# iotv3_595.net
KiCad netlist of a schematic drawn in Altium Designer
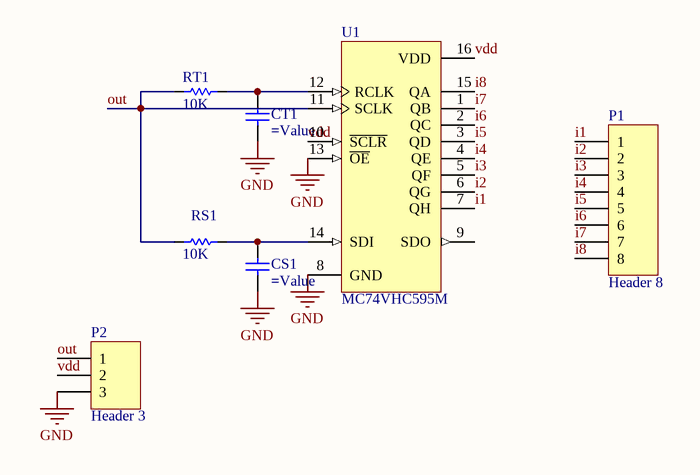
[diagram p0: iotv3 595.SchDoc]

(export (version "E")
  (design (tool "Eeschema 10.0.6"))
  (components
    (comp (ref "CS1")
      (value "~")
      (footprint "CAP 1206")
      (description "Capacitor")
      (libsource (lib "AltiumLib1") (part "Capacitor"))
    )
    (comp (ref "CT1")
      (value "~")
      (footprint "CAP 1206")
      (description "Capacitor")
      (libsource (lib "AltiumLib1") (part "Capacitor"))
    )
    (comp (ref "P1")
      (value "Header 8")
      (footprint "HDR1X8")
      (description "Header, 8-Pin")
      (fields (field (name "PUBLISHER") "Altium Limited"))
      (libsource (lib "Miscellaneous Connectors") (part "Header 8"))
    )
    (comp (ref "P2")
      (value "Header 3")
      (footprint "HDR1X3")
      (description "Header, 3-Pin")
      (fields (field (name "PUBLISHER") "Altium Limited"))
      (libsource (lib "Miscellaneous Connectors") (part "Header 3"))
    )
    (comp (ref "RS1")
      (value "10K")
      (footprint "RES 1206 (3216X08L)")
      (description "Resistor")
      (fields (field (name "TOLERANCE") "5%") (field (name "POWER") "1/4 W"))
      (libsource (lib "AltiumLib1") (part "Resistor"))
    )
    (comp (ref "RT1")
      (value "10K")
      (footprint "RES 1206 (3216X08L)")
      (description "Resistor")
      (fields (field (name "TOLERANCE") "5%") (field (name "POWER") "1/4 W"))
      (libsource (lib "AltiumLib1") (part "Resistor"))
    )
    (comp (ref "U1")
      (value "MC74VHC595M")
      (footprint "966-01_N")
      (description "8-Bit 3-State Shift Register with Output Storage Register")
      (fields (field (name "PUBLISHER") "Altium Limited"))
      (libsource (lib "ON Semi Logic Register") (part "MC74VHC595M"))
    )
  )
  (nets
    (net (code "1") (name "/i1") (class "Default")
      (node (ref "P1") (pin "1") (pinfunction "1_1") (pintype "passive"))
      (node (ref "U1") (pin "7") (pinfunction "QH_7") (pintype "tri_state"))
    )
    (net (code "2") (name "/i2") (class "Default")
      (node (ref "P1") (pin "2") (pinfunction "2_2") (pintype "passive"))
      (node (ref "U1") (pin "6") (pinfunction "QG_6") (pintype "tri_state"))
    )
    (net (code "3") (name "/i3") (class "Default")
      (node (ref "P1") (pin "3") (pinfunction "3_3") (pintype "passive"))
      (node (ref "U1") (pin "5") (pinfunction "QF_5") (pintype "tri_state"))
    )
    (net (code "4") (name "/i4") (class "Default")
      (node (ref "P1") (pin "4") (pinfunction "4_4") (pintype "passive"))
      (node (ref "U1") (pin "4") (pinfunction "QE_4") (pintype "tri_state"))
    )
    (net (code "5") (name "/i5") (class "Default")
      (node (ref "P1") (pin "5") (pinfunction "5_5") (pintype "passive"))
      (node (ref "U1") (pin "3") (pinfunction "QD_3") (pintype "tri_state"))
    )
    (net (code "6") (name "/i6") (class "Default")
      (node (ref "P1") (pin "6") (pinfunction "6_6") (pintype "passive"))
      (node (ref "U1") (pin "2") (pinfunction "QC_2") (pintype "tri_state"))
    )
    (net (code "7") (name "/i7") (class "Default")
      (node (ref "P1") (pin "7") (pinfunction "7_7") (pintype "passive"))
      (node (ref "U1") (pin "1") (pinfunction "QB_1") (pintype "tri_state"))
    )
    (net (code "8") (name "/i8") (class "Default")
      (node (ref "P1") (pin "8") (pinfunction "8_8") (pintype "passive"))
      (node (ref "U1") (pin "15") (pinfunction "QA_15") (pintype "tri_state"))
    )
    (net (code "9") (name "/out") (class "Default")
      (node (ref "P2") (pin "1") (pinfunction "1_1") (pintype "passive"))
      (node (ref "RS1") (pin "1") (pinfunction "1_1") (pintype "passive"))
      (node (ref "RT1") (pin "1") (pinfunction "1_1") (pintype "passive"))
      (node (ref "U1") (pin "11") (pinfunction "SCLK_11") (pintype "input"))
    )
    (net (code "10") (name "/vdd") (class "Default")
      (node (ref "P2") (pin "2") (pinfunction "2_2") (pintype "passive"))
      (node (ref "U1") (pin "10") (pinfunction "~{SCLR}_10") (pintype "input"))
      (node (ref "U1") (pin "16") (pinfunction "VDD_16") (pintype "power_in"))
    )
    (net (code "11") (name "GND") (class "Default")
      (node (ref "CS1") (pin "2") (pinfunction "-_2") (pintype "passive"))
      (node (ref "CT1") (pin "2") (pinfunction "-_2") (pintype "passive"))
      (node (ref "P2") (pin "3") (pinfunction "3_3") (pintype "passive"))
      (node (ref "U1") (pin "13") (pinfunction "~{OE}_13") (pintype "input"))
      (node (ref "U1") (pin "8") (pinfunction "GND_8") (pintype "power_in"))
    )
    (net (code "12") (name "Net-(CS1-+)") (class "Default")
      (node (ref "CS1") (pin "1") (pinfunction "+_1") (pintype "passive"))
      (node (ref "RS1") (pin "2") (pinfunction "2_2") (pintype "passive"))
      (node (ref "U1") (pin "14") (pinfunction "SDI_14") (pintype "input"))
    )
    (net (code "13") (name "Net-(CT1-+)") (class "Default")
      (node (ref "CT1") (pin "1") (pinfunction "+_1") (pintype "passive"))
      (node (ref "RT1") (pin "2") (pinfunction "2_2") (pintype "passive"))
      (node (ref "U1") (pin "12") (pinfunction "RCLK_12") (pintype "input"))
    )
    (net (code "14") (name "unconnected-(U1-SDO-Pad9)") (class "Default")
      (node (ref "U1") (pin "9") (pinfunction "SDO_9") (pintype "output"))
    )
  )
)
